# 1_Channel.net
KiCad netlist of a schematic drawn in EAGLE
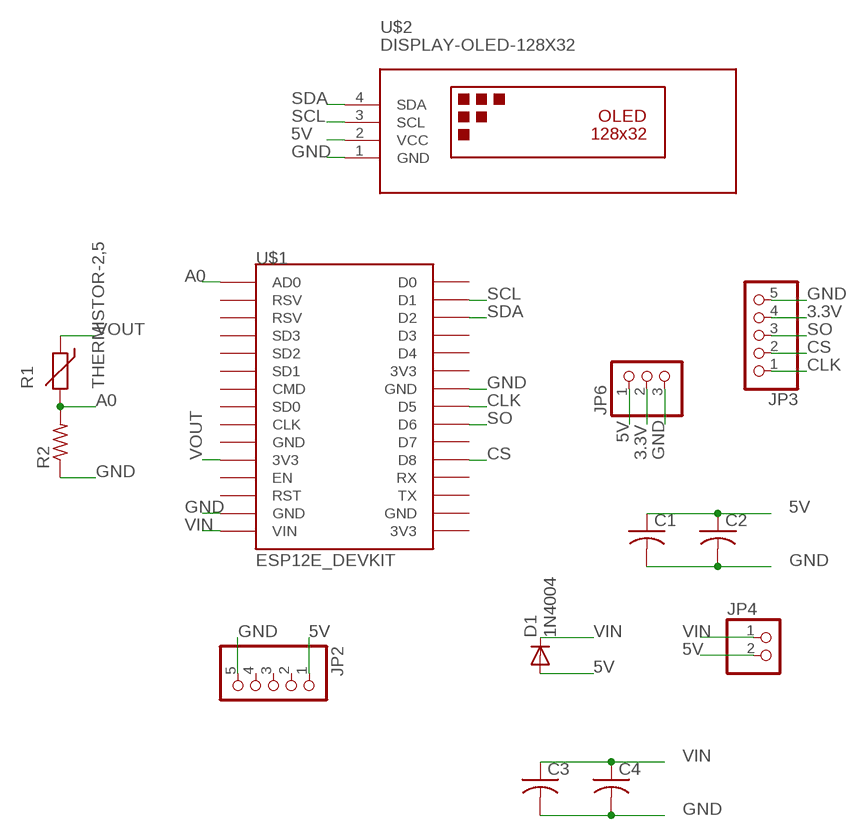
[diagram p0: schematic, sheet 1]

(export (version "E")
  (design (tool "Eeschema 10.0.6"))
  (components
    (comp (ref "C1")
      (value "C-US050-025X075")
      (footprint "eagle-import:C050-025X075")
      (libsource (lib "eagle-import") (part "C-US050-025X075"))
    )
    (comp (ref "C2")
      (value "C-US050-025X075")
      (footprint "eagle-import:C050-025X075")
      (libsource (lib "eagle-import") (part "C-US050-025X075"))
    )
    (comp (ref "C3")
      (value "C-US050-025X075")
      (footprint "eagle-import:C050-025X075")
      (libsource (lib "eagle-import") (part "C-US050-025X075"))
    )
    (comp (ref "C4")
      (value "C-US050-025X075")
      (footprint "eagle-import:C050-025X075")
      (libsource (lib "eagle-import") (part "C-US050-025X075"))
    )
    (comp (ref "D1")
      (value "1N4004")
      (footprint "eagle-import:DO41-10")
      (libsource (lib "eagle-import") (part "1N4004"))
    )
    (comp (ref "JP2")
      (value "PINHD-1X5")
      (footprint "eagle-import:1X05")
      (libsource (lib "eagle-import") (part "PINHD-1X5"))
    )
    (comp (ref "JP3")
      (value "PINHD-1X5")
      (footprint "eagle-import:1X05")
      (libsource (lib "eagle-import") (part "PINHD-1X5"))
    )
    (comp (ref "JP4")
      (value "PINHD-1X2")
      (footprint "eagle-import:1X02")
      (libsource (lib "eagle-import") (part "PINHD-1X2"))
    )
    (comp (ref "JP6")
      (value "PINHD-1X3CB")
      (footprint "eagle-import:1X03-CLEANBIG")
      (libsource (lib "eagle-import") (part "PINHD-1X3CB"))
    )
    (comp (ref "R1")
      (value "THERMISTOR-2,5")
      (footprint "eagle-import:RS-2,5")
      (libsource (lib "eagle-import") (part "THERMISTOR-2,5"))
    )
    (comp (ref "R2")
      (value "R-US_0207/7")
      (footprint "eagle-import:0207_7")
      (libsource (lib "eagle-import") (part "R-US_0207/7"))
    )
    (comp (ref "U$1")
      (value "ESP12E_DEVKIT")
      (footprint "eagle-import:ESP12E_DEVKIT")
      (libsource (lib "eagle-import") (part "ESP12E_DEVKIT"))
    )
    (comp (ref "U$2")
      (value "DISPLAY-OLED-128X32")
      (footprint "eagle-import:DISPLAY-OLED-128X32")
      (libsource (lib "eagle-import") (part "DISPLAY-OLED-128X32"))
    )
  )
  (nets
    (net (code "1") (name "/3.3V") (class "Default")
      (node (ref "JP3") (pin "4") (pinfunction "4_4") (pintype "passive"))
      (node (ref "JP6") (pin "2") (pinfunction "2_2") (pintype "passive"))
    )
    (net (code "2") (name "/5V") (class "Default")
      (node (ref "C1") (pin "1") (pinfunction "1_1") (pintype "passive"))
      (node (ref "C2") (pin "1") (pinfunction "1_1") (pintype "passive"))
      (node (ref "D1") (pin "A") (pinfunction "A_A") (pintype "passive"))
      (node (ref "JP2") (pin "1") (pinfunction "1_1") (pintype "passive"))
      (node (ref "JP4") (pin "2") (pinfunction "2_2") (pintype "passive"))
      (node (ref "JP6") (pin "1") (pinfunction "1_1") (pintype "passive"))
      (node (ref "U$2") (pin "2") (pinfunction "VCC_2") (pintype "power_in"))
    )
    (net (code "3") (name "/A0") (class "Default")
      (node (ref "R1") (pin "2") (pinfunction "2_2") (pintype "passive"))
      (node (ref "R2") (pin "2") (pinfunction "2_2") (pintype "passive"))
      (node (ref "U$1") (pin "AD0") (pinfunction "AD0_AD0") (pintype "bidirectional"))
    )
    (net (code "4") (name "/CLK") (class "Default")
      (node (ref "JP3") (pin "1") (pinfunction "1_1") (pintype "passive"))
      (node (ref "U$1") (pin "D5") (pinfunction "D5_D5") (pintype "bidirectional"))
    )
    (net (code "5") (name "/CS") (class "Default")
      (node (ref "JP3") (pin "2") (pinfunction "2_2") (pintype "passive"))
      (node (ref "U$1") (pin "D8") (pinfunction "D8_D8") (pintype "bidirectional"))
    )
    (net (code "6") (name "/GND") (class "Default")
      (node (ref "C1") (pin "2") (pinfunction "2_2") (pintype "passive"))
      (node (ref "C2") (pin "2") (pinfunction "2_2") (pintype "passive"))
      (node (ref "C3") (pin "2") (pinfunction "2_2") (pintype "passive"))
      (node (ref "C4") (pin "2") (pinfunction "2_2") (pintype "passive"))
      (node (ref "JP2") (pin "5") (pinfunction "5_5") (pintype "passive"))
      (node (ref "JP3") (pin "5") (pinfunction "5_5") (pintype "passive"))
      (node (ref "JP6") (pin "3") (pinfunction "3_3") (pintype "passive"))
      (node (ref "R2") (pin "1") (pinfunction "1_1") (pintype "passive"))
      (node (ref "U$1") (pin "GND@1") (pinfunction "GND_GND@1") (pintype "bidirectional"))
      (node (ref "U$1") (pin "GND@2") (pinfunction "GND_GND@2") (pintype "bidirectional"))
      (node (ref "U$2") (pin "1") (pinfunction "GND_1") (pintype "power_in"))
    )
    (net (code "7") (name "/SCL") (class "Default")
      (node (ref "U$1") (pin "D1") (pinfunction "D1_D1") (pintype "bidirectional"))
      (node (ref "U$2") (pin "3") (pinfunction "SCL_3") (pintype "bidirectional"))
    )
    (net (code "8") (name "/SDA") (class "Default")
      (node (ref "U$1") (pin "D2") (pinfunction "D2_D2") (pintype "bidirectional"))
      (node (ref "U$2") (pin "4") (pinfunction "SDA_4") (pintype "bidirectional"))
    )
    (net (code "9") (name "/SO") (class "Default")
      (node (ref "JP3") (pin "3") (pinfunction "3_3") (pintype "passive"))
      (node (ref "U$1") (pin "D6") (pinfunction "D6_D6") (pintype "bidirectional"))
    )
    (net (code "10") (name "/VIN") (class "Default")
      (node (ref "C3") (pin "1") (pinfunction "1_1") (pintype "passive"))
      (node (ref "C4") (pin "1") (pinfunction "1_1") (pintype "passive"))
      (node (ref "D1") (pin "C") (pinfunction "C_C") (pintype "passive"))
      (node (ref "JP4") (pin "1") (pinfunction "1_1") (pintype "passive"))
      (node (ref "U$1") (pin "VIN") (pinfunction "VIN_VIN") (pintype "bidirectional"))
    )
    (net (code "11") (name "/VOUT") (class "Default")
      (node (ref "R1") (pin "1") (pinfunction "1_1") (pintype "passive"))
      (node (ref "U$1") (pin "3V3@0") (pinfunction "3V3_3V3@0") (pintype "bidirectional"))
    )
    (net (code "12") (name "unconnected-(JP2-Pad2)") (class "Default")
      (node (ref "JP2") (pin "2") (pinfunction "2_2") (pintype "passive"))
    )
    (net (code "13") (name "unconnected-(JP2-Pad3)") (class "Default")
      (node (ref "JP2") (pin "3") (pinfunction "3_3") (pintype "passive"))
    )
    (net (code "14") (name "unconnected-(JP2-Pad4)") (class "Default")
      (node (ref "JP2") (pin "4") (pinfunction "4_4") (pintype "passive"))
    )
    (net (code "15") (name "unconnected-(U$1-3V3-Pad3V3@1)") (class "Default")
      (node (ref "U$1") (pin "3V3@1") (pinfunction "3V3_3V3@1") (pintype "bidirectional"))
    )
    (net (code "16") (name "unconnected-(U$1-3V3-Pad3V3@2)") (class "Default")
      (node (ref "U$1") (pin "3V3@2") (pinfunction "3V3_3V3@2") (pintype "bidirectional"))
    )
    (net (code "17") (name "unconnected-(U$1-GND-PadGND@0)") (class "Default")
      (node (ref "U$1") (pin "GND@0") (pinfunction "GND_GND@0") (pintype "bidirectional"))
    )
    (net (code "18") (name "unconnected-(U$1-GND-PadGND@3)") (class "Default")
      (node (ref "U$1") (pin "GND@3") (pinfunction "GND_GND@3") (pintype "bidirectional"))
    )
    (net (code "19") (name "unconnected-(U$1-PadCLK)") (class "Default")
      (node (ref "U$1") (pin "CLK") (pinfunction "CLK_CLK") (pintype "bidirectional"))
    )
    (net (code "20") (name "unconnected-(U$1-PadCMD)") (class "Default")
      (node (ref "U$1") (pin "CMD") (pinfunction "CMD_CMD") (pintype "bidirectional"))
    )
    (net (code "21") (name "unconnected-(U$1-PadD0)") (class "Default")
      (node (ref "U$1") (pin "D0") (pinfunction "D0_D0") (pintype "bidirectional"))
    )
    (net (code "22") (name "unconnected-(U$1-PadD3)") (class "Default")
      (node (ref "U$1") (pin "D3") (pinfunction "D3_D3") (pintype "bidirectional"))
    )
    (net (code "23") (name "unconnected-(U$1-PadD4)") (class "Default")
      (node (ref "U$1") (pin "D4") (pinfunction "D4_D4") (pintype "bidirectional"))
    )
    (net (code "24") (name "unconnected-(U$1-PadD7)") (class "Default")
      (node (ref "U$1") (pin "D7") (pinfunction "D7_D7") (pintype "bidirectional"))
    )
    (net (code "25") (name "unconnected-(U$1-PadEN)") (class "Default")
      (node (ref "U$1") (pin "EN") (pinfunction "EN_EN") (pintype "bidirectional"))
    )
    (net (code "26") (name "unconnected-(U$1-PadRST)") (class "Default")
      (node (ref "U$1") (pin "RST") (pinfunction "RST_RST") (pintype "bidirectional"))
    )
    (net (code "27") (name "unconnected-(U$1-PadRX)") (class "Default")
      (node (ref "U$1") (pin "RX") (pinfunction "RX_RX") (pintype "bidirectional"))
    )
    (net (code "28") (name "unconnected-(U$1-PadSD0)") (class "Default")
      (node (ref "U$1") (pin "SD0") (pinfunction "SD0_SD0") (pintype "bidirectional"))
    )
    (net (code "29") (name "unconnected-(U$1-PadSD1)") (class "Default")
      (node (ref "U$1") (pin "SD1") (pinfunction "SD1_SD1") (pintype "bidirectional"))
    )
    (net (code "30") (name "unconnected-(U$1-PadSD2)") (class "Default")
      (node (ref "U$1") (pin "SD2") (pinfunction "SD2_SD2") (pintype "bidirectional"))
    )
    (net (code "31") (name "unconnected-(U$1-PadSD3)") (class "Default")
      (node (ref "U$1") (pin "SD3") (pinfunction "SD3_SD3") (pintype "bidirectional"))
    )
    (net (code "32") (name "unconnected-(U$1-PadTX)") (class "Default")
      (node (ref "U$1") (pin "TX") (pinfunction "TX_TX") (pintype "bidirectional"))
    )
    (net (code "33") (name "unconnected-(U$1-RSV-PadRSV@0)") (class "Default")
      (node (ref "U$1") (pin "RSV@0") (pinfunction "RSV_RSV@0") (pintype "bidirectional"))
    )
    (net (code "34") (name "unconnected-(U$1-RSV-PadRSV@1)") (class "Default")
      (node (ref "U$1") (pin "RSV@1") (pinfunction "RSV_RSV@1") (pintype "bidirectional"))
    )
  )
)
